# Sensors.net
KiCad netlist of a schematic drawn in Altium Designer
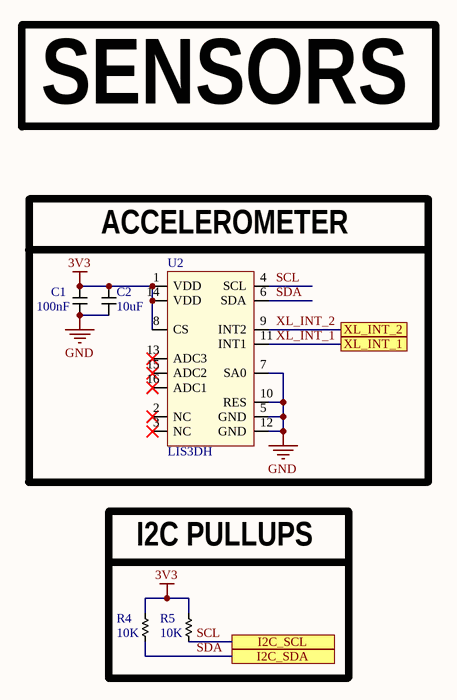
[diagram p0: Sensors.SchDoc]

(export (version "E")
  (design (tool "Eeschema 10.0.6"))
  (components
    (comp (ref "C1")
      (value "100nF")
      (footprint "CAP_0603_HIGH")
      (description "0603 Capacitor")
      (libsource (lib "smLib") (part "Capacitor_0603"))
    )
    (comp (ref "C2")
      (value "10uF")
      (footprint "CAP_0603_HIGH")
      (description "0603 Capacitor")
      (libsource (lib "smLib") (part "Capacitor_0603"))
    )
    (comp (ref "R4")
      (value "10K")
      (footprint "RES_0603_HIGH")
      (description "0603 Resistor")
      (libsource (lib "smLib") (part "Resistor_0603"))
    )
    (comp (ref "R5")
      (value "10K")
      (footprint "RES_0603_HIGH")
      (description "0603 Resistor")
      (libsource (lib "smLib") (part "Resistor_0603"))
    )
    (comp (ref "U2")
      (value "LIS3DH")
      (footprint "LIS3DH")
      (description "LIS3DH ACCEL 2-16G I2C/SPI 16LGA")
      (libsource (lib "smLib") (part "LIS3DH"))
    )
  )
  (nets
    (net (code "1") (name "/SCL") (class "Default")
      (node (ref "R5") (pin "1") (pinfunction "1_1") (pintype "passive"))
      (node (ref "U2") (pin "4") (pinfunction "SCL_4") (pintype "passive"))
    )
    (net (code "2") (name "/SDA") (class "Default")
      (node (ref "R4") (pin "1") (pinfunction "1_1") (pintype "passive"))
      (node (ref "U2") (pin "6") (pinfunction "SDA_6") (pintype "passive"))
    )
    (net (code "3") (name "/XL_INT_1") (class "Default")
      (node (ref "U2") (pin "11") (pinfunction "INT1_11") (pintype "passive"))
    )
    (net (code "4") (name "/XL_INT_2") (class "Default")
      (node (ref "U2") (pin "9") (pinfunction "INT2_9") (pintype "passive"))
    )
    (net (code "5") (name "3V3") (class "Default")
      (node (ref "C1") (pin "1") (pinfunction "1_1") (pintype "passive"))
      (node (ref "C2") (pin "1") (pinfunction "1_1") (pintype "passive"))
      (node (ref "R4") (pin "2") (pinfunction "2_2") (pintype "passive"))
      (node (ref "R5") (pin "2") (pinfunction "2_2") (pintype "passive"))
      (node (ref "U2") (pin "1") (pinfunction "VDD_1") (pintype "passive"))
      (node (ref "U2") (pin "14") (pinfunction "VDD_14") (pintype "passive"))
      (node (ref "U2") (pin "8") (pinfunction "CS_8") (pintype "passive"))
    )
    (net (code "6") (name "GND") (class "Default")
      (node (ref "C1") (pin "2") (pinfunction "2_2") (pintype "passive"))
      (node (ref "C2") (pin "2") (pinfunction "2_2") (pintype "passive"))
      (node (ref "U2") (pin "10") (pinfunction "RES_10") (pintype "passive"))
      (node (ref "U2") (pin "12") (pinfunction "GND_12") (pintype "passive"))
      (node (ref "U2") (pin "5") (pinfunction "GND_5") (pintype "passive"))
      (node (ref "U2") (pin "7") (pinfunction "SA0_7") (pintype "passive"))
    )
    (net (code "7") (name "unconnected-(U2-ADC1-Pad16)") (class "Default")
      (node (ref "U2") (pin "16") (pinfunction "ADC1_16") (pintype "passive+no_connect"))
    )
    (net (code "8") (name "unconnected-(U2-ADC2-Pad15)") (class "Default")
      (node (ref "U2") (pin "15") (pinfunction "ADC2_15") (pintype "passive+no_connect"))
    )
    (net (code "9") (name "unconnected-(U2-ADC3-Pad13)") (class "Default")
      (node (ref "U2") (pin "13") (pinfunction "ADC3_13") (pintype "passive+no_connect"))
    )
    (net (code "10") (name "unconnected-(U2-NC-Pad2)") (class "Default")
      (node (ref "U2") (pin "2") (pinfunction "NC_2") (pintype "passive+no_connect"))
    )
    (net (code "11") (name "unconnected-(U2-NC-Pad3)") (class "Default")
      (node (ref "U2") (pin "3") (pinfunction "NC_3") (pintype "passive+no_connect"))
    )
  )
)
